# Sheet_1_2021-11-20.net
KiCad netlist of a schematic drawn in Altium Designer
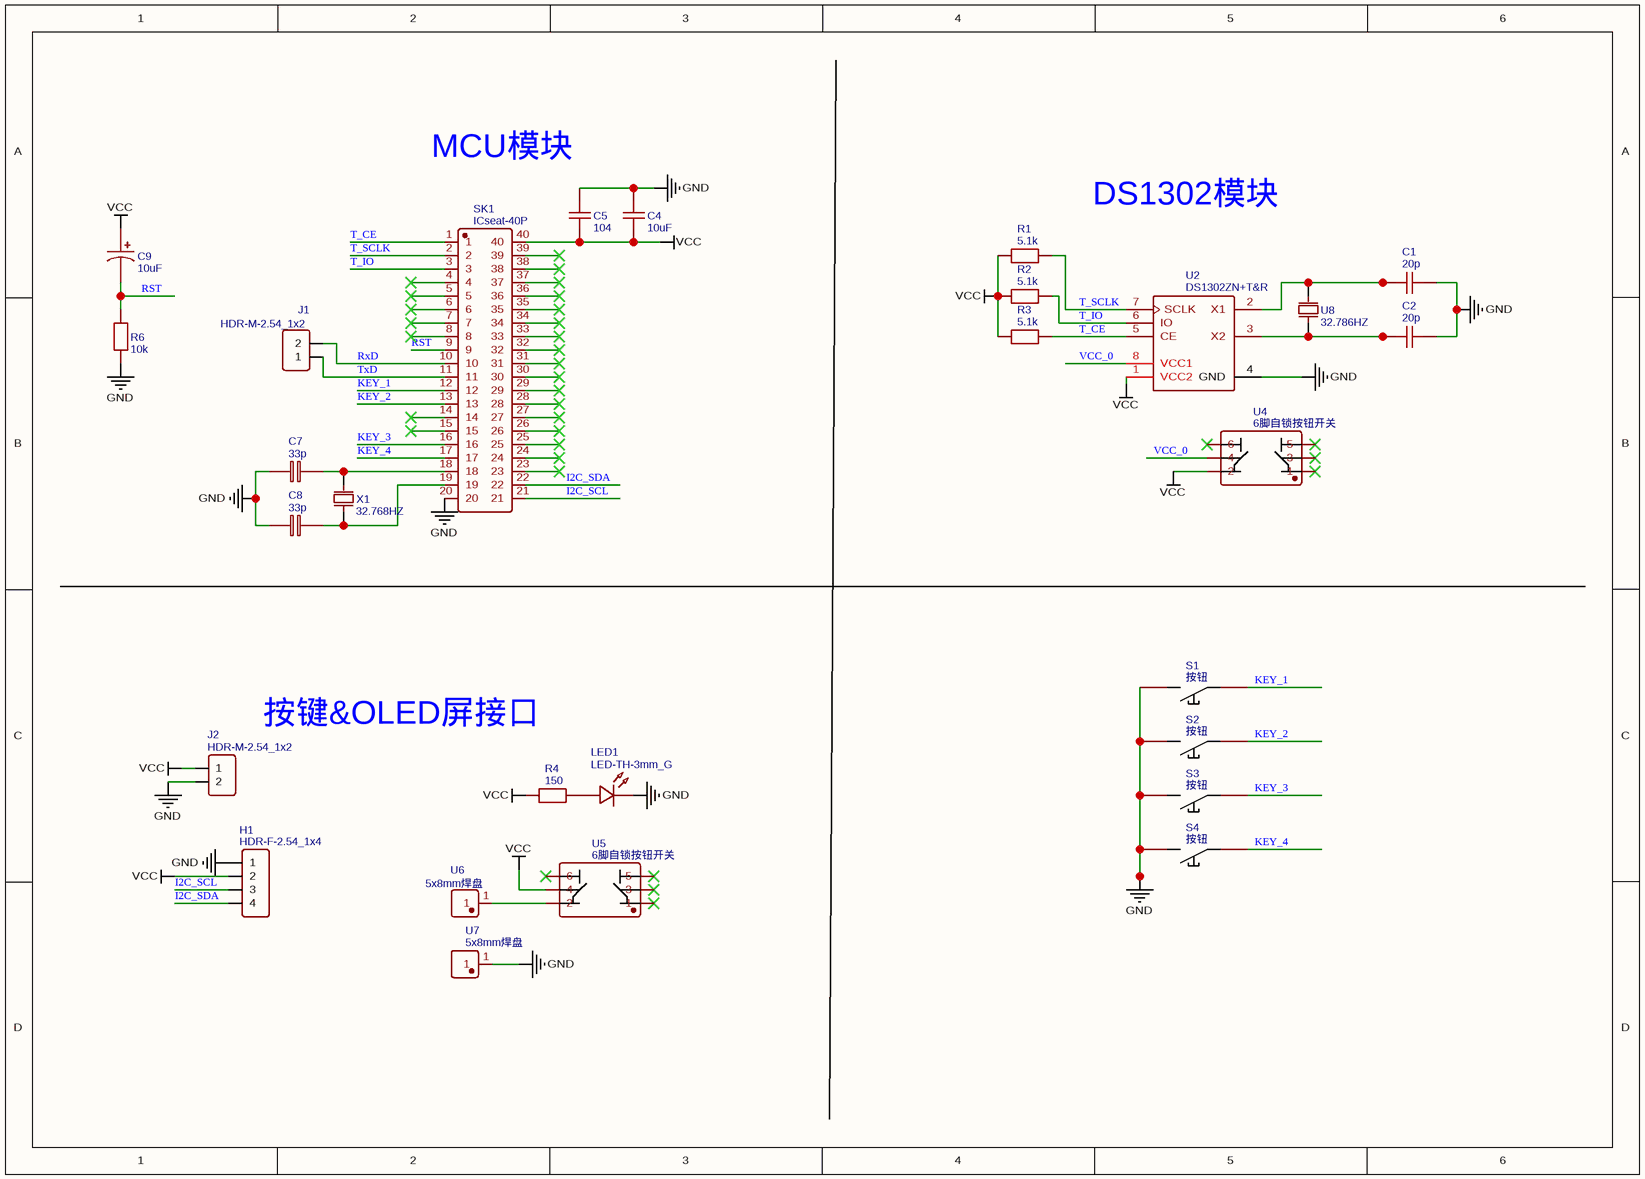
[diagram p0: Sheet_1_2021-11-20.schdoc]

(export (version "E")
  (design (tool "Eeschema 10.0.6"))
  (components
    (comp (ref "C1")
      (value "20p")
      (fields (field (name "CONTRIBUTOR") "LCEDA_Lib"))
      (libsource (lib "altium-import") (part "root_0_20p_"))
    )
    (comp (ref "C2")
      (value "20p")
      (fields (field (name "CONTRIBUTOR") "LCEDA_Lib"))
      (libsource (lib "altium-import") (part "root_0_20p_"))
    )
    (comp (ref "C4")
      (value "10uF")
      (fields (field (name "CONTRIBUTOR") "LCEDA_Lib"))
      (libsource (lib "") (part "root_3_10uF__1"))
    )
    (comp (ref "C5")
      (value "104")
      (fields (field (name "CONTRIBUTOR") "LCEDA_Lib"))
      (libsource (lib "altium-import") (part "root_3_104_"))
    )
    (comp (ref "C7")
      (value "33p")
      (fields (field (name "CONTRIBUTOR") "LCEDA_Lib"))
      (libsource (lib "altium-import") (part "root_0_33p_"))
    )
    (comp (ref "C8")
      (value "33p")
      (fields (field (name "CONTRIBUTOR") "LCEDA_Lib"))
      (libsource (lib "altium-import") (part "root_0_33p_"))
    )
    (comp (ref "C9")
      (value "10uF")
      (fields (field (name "CONTRIBUTOR") "LCEDA_Lib"))
      (libsource (lib "altium-import") (part "root_3_10uF_"))
    )
    (comp (ref "H1")
      (value "HDR-F-2.54_1x4")
      (fields (field (name "BOM_SUPPLIER PART") "C225501") (field (name "CONTRIBUTOR") "LCEDA_Lib"))
      (libsource (lib "altium-import") (part "root_0_HDR-F-2.54_1x4_"))
    )
    (comp (ref "J1")
      (value "HDR-M-2.54_1x2")
      (fields (field (name "BOM_SUPPLIER PART") "C124375") (field (name "CONTRIBUTOR") "LCEDA_Lib"))
      (libsource (lib "altium-import") (part "root_2_HDR-M-2.54_1x2_"))
    )
    (comp (ref "J2")
      (value "HDR-M-2.54_1x2")
      (fields (field (name "BOM_SUPPLIER PART") "C124375") (field (name "CONTRIBUTOR") "LCEDA_Lib"))
      (libsource (lib "altium-import") (part "root_0_HDR-M-2.54_1x2_"))
    )
    (comp (ref "LED1")
      (value "LED-TH-3mm_G")
      (fields
        (field (name "BOM_MANUFACTURER PART") "204-10SYGD/S530-E3")
        (field (name "BOM_SUPPLIER PART") "C85161")
        (field (name "CONTRIBUTOR") "LCEDA_Lib")
      )
      (libsource (lib "altium-import") (part "root_0_LED-TH-3mm_G_"))
    )
    (comp (ref "R1")
      (value "5.1k")
      (fields (field (name "CONTRIBUTOR") "LCEDA_Lib"))
      (libsource (lib "altium-import") (part "root_0_5.1k_"))
    )
    (comp (ref "R2")
      (value "5.1k")
      (fields (field (name "CONTRIBUTOR") "LCEDA_Lib"))
      (libsource (lib "altium-import") (part "root_0_5.1k_"))
    )
    (comp (ref "R3")
      (value "5.1k")
      (fields (field (name "CONTRIBUTOR") "LCEDA_Lib"))
      (libsource (lib "altium-import") (part "root_0_5.1k_"))
    )
    (comp (ref "R4")
      (value "150")
      (fields (field (name "CONTRIBUTOR") "LCEDA_Lib"))
      (libsource (lib "altium-import") (part "root_0_150_"))
    )
    (comp (ref "R6")
      (value "10k")
      (fields (field (name "CONTRIBUTOR") "LCEDA_Lib"))
      (libsource (lib "altium-import") (part "root_1_10k_"))
    )
    (comp (ref "S1")
      (value "按钮")
      (fields (field (name "CONTRIBUTOR") "lijnu123"))
      (libsource (lib "altium-import") (part "root_0_按钮_"))
    )
    (comp (ref "S2")
      (value "按钮")
      (fields (field (name "CONTRIBUTOR") "lijnu123"))
      (libsource (lib "altium-import") (part "root_0_按钮_"))
    )
    (comp (ref "S3")
      (value "按钮")
      (fields (field (name "CONTRIBUTOR") "lijnu123"))
      (libsource (lib "altium-import") (part "root_0_按钮_"))
    )
    (comp (ref "S4")
      (value "按钮")
      (fields (field (name "CONTRIBUTOR") "lijnu123"))
      (libsource (lib "altium-import") (part "root_0_按钮_"))
    )
    (comp (ref "SK1")
      (value "ICseat-40P")
      (fields (field (name "BOM_SUPPLIER PART") "C2332") (field (name "CONTRIBUTOR") "LCSC"))
      (libsource (lib "altium-import") (part "root_0_ICseat-40P_"))
    )
    (comp (ref "U2")
      (value "DS1302ZN+T&R")
      (fields (field (name "BOM_SUPPLIER PART") "C14334"))
      (libsource (lib "altium-import") (part "root_0_DS1302ZN+T&R_"))
    )
    (comp (ref "U4")
      (value "6脚自锁按钮开关")
      (fields (field (name "CONTRIBUTOR") "haorandad"))
      (libsource (lib "altium-import") (part "root_2_6脚自锁按钮开关_"))
    )
    (comp (ref "U5")
      (value "6脚自锁按钮开关")
      (fields (field (name "CONTRIBUTOR") "haorandad"))
      (libsource (lib "altium-import") (part "root_2_6脚自锁按钮开关_"))
    )
    (comp (ref "U6")
      (value "5x8mm焊盘")
      (fields (field (name "CONTRIBUTOR") "jidantou"))
      (libsource (lib "altium-import") (part "root_2_5x8mm焊盘_"))
    )
    (comp (ref "U7")
      (value "5x8mm焊盘")
      (fields (field (name "CONTRIBUTOR") "jidantou"))
      (libsource (lib "altium-import") (part "root_2_5x8mm焊盘_"))
    )
    (comp (ref "U8")
      (value "32.786HZ晶振_宽焊盘")
      (fields (field (name "CONTRIBUTOR") "jidantou"))
      (libsource (lib "altium-import") (part "root_0_32.786HZ晶振_宽焊盘_"))
    )
    (comp (ref "X1")
      (value "32.768HZ")
      (fields
        (field (name "BOM_SUPPLIER PART") "C443528")
        (field (name "BOM_MANUFACTURER PART") "49SAC08000∞2060")
        (field (name "CONTRIBUTOR") "LCSC")
      )
      (libsource (lib "altium-import") (part "root_1_32.768HZ_"))
    )
  )
  (nets
    (net (code "1") (name "/I2C_SCL") (class "Default")
      (node (ref "H1") (pin "3") (pinfunction "3_3") (pintype "passive"))
      (node (ref "SK1") (pin "21") (pinfunction "21_21") (pintype "passive"))
    )
    (net (code "2") (name "/I2C_SDA") (class "Default")
      (node (ref "H1") (pin "4") (pinfunction "4_4") (pintype "passive"))
      (node (ref "SK1") (pin "22") (pinfunction "22_22") (pintype "passive"))
    )
    (net (code "3") (name "/KEY_1") (class "Default")
      (node (ref "S1") (pin "2") (pinfunction "2_2") (pintype "passive"))
      (node (ref "SK1") (pin "12") (pinfunction "12_12") (pintype "passive"))
    )
    (net (code "4") (name "/KEY_2") (class "Default")
      (node (ref "S2") (pin "2") (pinfunction "2_2") (pintype "passive"))
      (node (ref "SK1") (pin "13") (pinfunction "13_13") (pintype "passive"))
    )
    (net (code "5") (name "/KEY_3") (class "Default")
      (node (ref "S3") (pin "2") (pinfunction "2_2") (pintype "passive"))
      (node (ref "SK1") (pin "16") (pinfunction "16_16") (pintype "passive"))
    )
    (net (code "6") (name "/KEY_4") (class "Default")
      (node (ref "S4") (pin "2") (pinfunction "2_2") (pintype "passive"))
      (node (ref "SK1") (pin "17") (pinfunction "17_17") (pintype "passive"))
    )
    (net (code "7") (name "/RST") (class "Default")
      (node (ref "C9") (pin "2") (pinfunction "2_2") (pintype "passive"))
      (node (ref "R6") (pin "2") (pinfunction "2_2") (pintype "passive"))
      (node (ref "SK1") (pin "9") (pinfunction "9_9") (pintype "passive"))
    )
    (net (code "8") (name "/RxD") (class "Default")
      (node (ref "J1") (pin "2") (pinfunction "2_2") (pintype "passive"))
      (node (ref "SK1") (pin "10") (pinfunction "10_10") (pintype "passive"))
    )
    (net (code "9") (name "/T_CE") (class "Default")
      (node (ref "R3") (pin "2") (pinfunction "2_2") (pintype "passive"))
      (node (ref "SK1") (pin "1") (pinfunction "1_1") (pintype "passive"))
      (node (ref "U2") (pin "5") (pinfunction "CE_5") (pintype "passive"))
    )
    (net (code "10") (name "/T_IO") (class "Default")
      (node (ref "R2") (pin "2") (pinfunction "2_2") (pintype "passive"))
      (node (ref "SK1") (pin "3") (pinfunction "3_3") (pintype "passive"))
      (node (ref "U2") (pin "6") (pinfunction "IO_6") (pintype "passive"))
    )
    (net (code "11") (name "/T_SCLK") (class "Default")
      (node (ref "R1") (pin "2") (pinfunction "2_2") (pintype "passive"))
      (node (ref "SK1") (pin "2") (pinfunction "2_2") (pintype "passive"))
      (node (ref "U2") (pin "7") (pinfunction "SCLK_7") (pintype "passive"))
    )
    (net (code "12") (name "/TxD") (class "Default")
      (node (ref "J1") (pin "1") (pinfunction "1_1") (pintype "passive"))
      (node (ref "SK1") (pin "11") (pinfunction "11_11") (pintype "passive"))
    )
    (net (code "13") (name "/VCC_0") (class "Default")
      (node (ref "U2") (pin "8") (pinfunction "VCC1_8") (pintype "passive"))
      (node (ref "U4") (pin "4") (pinfunction "4_4") (pintype "passive"))
    )
    (net (code "14") (name "GND") (class "Default")
      (node (ref "C1") (pin "2") (pinfunction "2_2") (pintype "passive"))
      (node (ref "C2") (pin "2") (pinfunction "2_2") (pintype "passive"))
      (node (ref "C4") (pin "1") (pinfunction "1_1") (pintype "passive"))
      (node (ref "C5") (pin "1") (pinfunction "1_1") (pintype "passive"))
      (node (ref "C7") (pin "1") (pinfunction "1_1") (pintype "passive"))
      (node (ref "C8") (pin "1") (pinfunction "1_1") (pintype "passive"))
      (node (ref "H1") (pin "1") (pinfunction "1_1") (pintype "passive"))
      (node (ref "J2") (pin "2") (pinfunction "2_2") (pintype "passive"))
      (node (ref "LED1") (pin "2") (pinfunction "2_2") (pintype "passive"))
      (node (ref "R6") (pin "1") (pinfunction "1_1") (pintype "passive"))
      (node (ref "S1") (pin "4") (pinfunction "4_4") (pintype "passive"))
      (node (ref "S2") (pin "4") (pinfunction "4_4") (pintype "passive"))
      (node (ref "S3") (pin "4") (pinfunction "4_4") (pintype "passive"))
      (node (ref "S4") (pin "4") (pinfunction "4_4") (pintype "passive"))
      (node (ref "SK1") (pin "20") (pinfunction "20_20") (pintype "passive"))
      (node (ref "U2") (pin "4") (pinfunction "GND_4") (pintype "passive"))
      (node (ref "U7") (pin "1") (pinfunction "1_1") (pintype "passive"))
    )
    (net (code "15") (name "Net-(LED1-Pad1)") (class "Default")
      (node (ref "LED1") (pin "1") (pinfunction "1_1") (pintype "passive"))
      (node (ref "R4") (pin "2") (pinfunction "2_2") (pintype "passive"))
    )
    (net (code "16") (name "Net-(U2-X1)") (class "Default")
      (node (ref "C1") (pin "1") (pinfunction "1_1") (pintype "passive"))
      (node (ref "U2") (pin "2") (pinfunction "X1_2") (pintype "passive"))
      (node (ref "U8") (pin "1") (pinfunction "OSC1_1") (pintype "passive"))
    )
    (net (code "17") (name "Net-(U2-X2)") (class "Default")
      (node (ref "C2") (pin "1") (pinfunction "1_1") (pintype "passive"))
      (node (ref "U2") (pin "3") (pinfunction "X2_3") (pintype "passive"))
      (node (ref "U8") (pin "2") (pinfunction "OSC2_2") (pintype "passive"))
    )
    (net (code "18") (name "Net-(U5-Pad2)") (class "Default")
      (node (ref "U5") (pin "2") (pinfunction "2_2") (pintype "passive"))
      (node (ref "U6") (pin "1") (pinfunction "1_1") (pintype "passive"))
    )
    (net (code "19") (name "Net-(X1-OSC1)") (class "Default")
      (node (ref "C8") (pin "2") (pinfunction "2_2") (pintype "passive"))
      (node (ref "SK1") (pin "19") (pinfunction "19_19") (pintype "passive"))
      (node (ref "X1") (pin "1") (pinfunction "OSC1_1") (pintype "passive"))
    )
    (net (code "20") (name "Net-(X1-OSC2)") (class "Default")
      (node (ref "C7") (pin "2") (pinfunction "2_2") (pintype "passive"))
      (node (ref "SK1") (pin "18") (pinfunction "18_18") (pintype "passive"))
      (node (ref "X1") (pin "2") (pinfunction "OSC2_2") (pintype "passive"))
    )
    (net (code "21") (name "VCC") (class "Default")
      (node (ref "C4") (pin "2") (pinfunction "2_2") (pintype "passive"))
      (node (ref "C5") (pin "2") (pinfunction "2_2") (pintype "passive"))
      (node (ref "C9") (pin "1") (pinfunction "1_1") (pintype "passive"))
      (node (ref "H1") (pin "2") (pinfunction "2_2") (pintype "passive"))
      (node (ref "J2") (pin "1") (pinfunction "1_1") (pintype "passive"))
      (node (ref "R1") (pin "1") (pinfunction "1_1") (pintype "passive"))
      (node (ref "R2") (pin "1") (pinfunction "1_1") (pintype "passive"))
      (node (ref "R3") (pin "1") (pinfunction "1_1") (pintype "passive"))
      (node (ref "R4") (pin "1") (pinfunction "1_1") (pintype "passive"))
      (node (ref "SK1") (pin "40") (pinfunction "40_40") (pintype "passive"))
      (node (ref "U2") (pin "1") (pinfunction "VCC2_1") (pintype "passive"))
      (node (ref "U4") (pin "2") (pinfunction "2_2") (pintype "passive"))
      (node (ref "U5") (pin "4") (pinfunction "4_4") (pintype "passive"))
    )
    (net (code "22") (name "unconnected-(SK1-Pad4)") (class "Default")
      (node (ref "SK1") (pin "4") (pinfunction "4_4") (pintype "passive+no_connect"))
    )
    (net (code "23") (name "unconnected-(SK1-Pad5)") (class "Default")
      (node (ref "SK1") (pin "5") (pinfunction "5_5") (pintype "passive+no_connect"))
    )
    (net (code "24") (name "unconnected-(SK1-Pad6)") (class "Default")
      (node (ref "SK1") (pin "6") (pinfunction "6_6") (pintype "passive+no_connect"))
    )
    (net (code "25") (name "unconnected-(SK1-Pad7)") (class "Default")
      (node (ref "SK1") (pin "7") (pinfunction "7_7") (pintype "passive+no_connect"))
    )
    (net (code "26") (name "unconnected-(SK1-Pad8)") (class "Default")
      (node (ref "SK1") (pin "8") (pinfunction "8_8") (pintype "passive+no_connect"))
    )
    (net (code "27") (name "unconnected-(SK1-Pad14)") (class "Default")
      (node (ref "SK1") (pin "14") (pinfunction "14_14") (pintype "passive+no_connect"))
    )
    (net (code "28") (name "unconnected-(SK1-Pad15)") (class "Default")
      (node (ref "SK1") (pin "15") (pinfunction "15_15") (pintype "passive+no_connect"))
    )
    (net (code "29") (name "unconnected-(SK1-Pad23)") (class "Default")
      (node (ref "SK1") (pin "23") (pinfunction "23_23") (pintype "passive+no_connect"))
    )
    (net (code "30") (name "unconnected-(SK1-Pad24)") (class "Default")
      (node (ref "SK1") (pin "24") (pinfunction "24_24") (pintype "passive+no_connect"))
    )
    (net (code "31") (name "unconnected-(SK1-Pad25)") (class "Default")
      (node (ref "SK1") (pin "25") (pinfunction "25_25") (pintype "passive+no_connect"))
    )
    (net (code "32") (name "unconnected-(SK1-Pad26)") (class "Default")
      (node (ref "SK1") (pin "26") (pinfunction "26_26") (pintype "passive+no_connect"))
    )
    (net (code "33") (name "unconnected-(SK1-Pad27)") (class "Default")
      (node (ref "SK1") (pin "27") (pinfunction "27_27") (pintype "passive+no_connect"))
    )
    (net (code "34") (name "unconnected-(SK1-Pad28)") (class "Default")
      (node (ref "SK1") (pin "28") (pinfunction "28_28") (pintype "passive+no_connect"))
    )
    (net (code "35") (name "unconnected-(SK1-Pad29)") (class "Default")
      (node (ref "SK1") (pin "29") (pinfunction "29_29") (pintype "passive+no_connect"))
    )
    (net (code "36") (name "unconnected-(SK1-Pad30)") (class "Default")
      (node (ref "SK1") (pin "30") (pinfunction "30_30") (pintype "passive+no_connect"))
    )
    (net (code "37") (name "unconnected-(SK1-Pad31)") (class "Default")
      (node (ref "SK1") (pin "31") (pinfunction "31_31") (pintype "passive+no_connect"))
    )
    (net (code "38") (name "unconnected-(SK1-Pad32)") (class "Default")
      (node (ref "SK1") (pin "32") (pinfunction "32_32") (pintype "passive+no_connect"))
    )
    (net (code "39") (name "unconnected-(SK1-Pad33)") (class "Default")
      (node (ref "SK1") (pin "33") (pinfunction "33_33") (pintype "passive+no_connect"))
    )
    (net (code "40") (name "unconnected-(SK1-Pad34)") (class "Default")
      (node (ref "SK1") (pin "34") (pinfunction "34_34") (pintype "passive+no_connect"))
    )
    (net (code "41") (name "unconnected-(SK1-Pad35)") (class "Default")
      (node (ref "SK1") (pin "35") (pinfunction "35_35") (pintype "passive+no_connect"))
    )
    (net (code "42") (name "unconnected-(SK1-Pad36)") (class "Default")
      (node (ref "SK1") (pin "36") (pinfunction "36_36") (pintype "passive+no_connect"))
    )
    (net (code "43") (name "unconnected-(SK1-Pad37)") (class "Default")
      (node (ref "SK1") (pin "37") (pinfunction "37_37") (pintype "passive+no_connect"))
    )
    (net (code "44") (name "unconnected-(SK1-Pad38)") (class "Default")
      (node (ref "SK1") (pin "38") (pinfunction "38_38") (pintype "passive+no_connect"))
    )
    (net (code "45") (name "unconnected-(SK1-Pad39)") (class "Default")
      (node (ref "SK1") (pin "39") (pinfunction "39_39") (pintype "passive+no_connect"))
    )
    (net (code "46") (name "unconnected-(U4-Pad1)") (class "Default")
      (node (ref "U4") (pin "1") (pinfunction "1_1") (pintype "passive+no_connect"))
    )
    (net (code "47") (name "unconnected-(U4-Pad3)") (class "Default")
      (node (ref "U4") (pin "3") (pinfunction "3_3") (pintype "passive+no_connect"))
    )
    (net (code "48") (name "unconnected-(U4-Pad5)") (class "Default")
      (node (ref "U4") (pin "5") (pinfunction "5_5") (pintype "passive+no_connect"))
    )
    (net (code "49") (name "unconnected-(U4-Pad6)") (class "Default")
      (node (ref "U4") (pin "6") (pinfunction "6_6") (pintype "passive+no_connect"))
    )
    (net (code "50") (name "unconnected-(U5-Pad1)") (class "Default")
      (node (ref "U5") (pin "1") (pinfunction "1_1") (pintype "passive+no_connect"))
    )
    (net (code "51") (name "unconnected-(U5-Pad3)") (class "Default")
      (node (ref "U5") (pin "3") (pinfunction "3_3") (pintype "passive+no_connect"))
    )
    (net (code "52") (name "unconnected-(U5-Pad5)") (class "Default")
      (node (ref "U5") (pin "5") (pinfunction "5_5") (pintype "passive+no_connect"))
    )
    (net (code "53") (name "unconnected-(U5-Pad6)") (class "Default")
      (node (ref "U5") (pin "6") (pinfunction "6_6") (pintype "passive+no_connect"))
    )
  )
)
